# Status_LEDs.net
KiCad netlist of a schematic drawn in Altium Designer
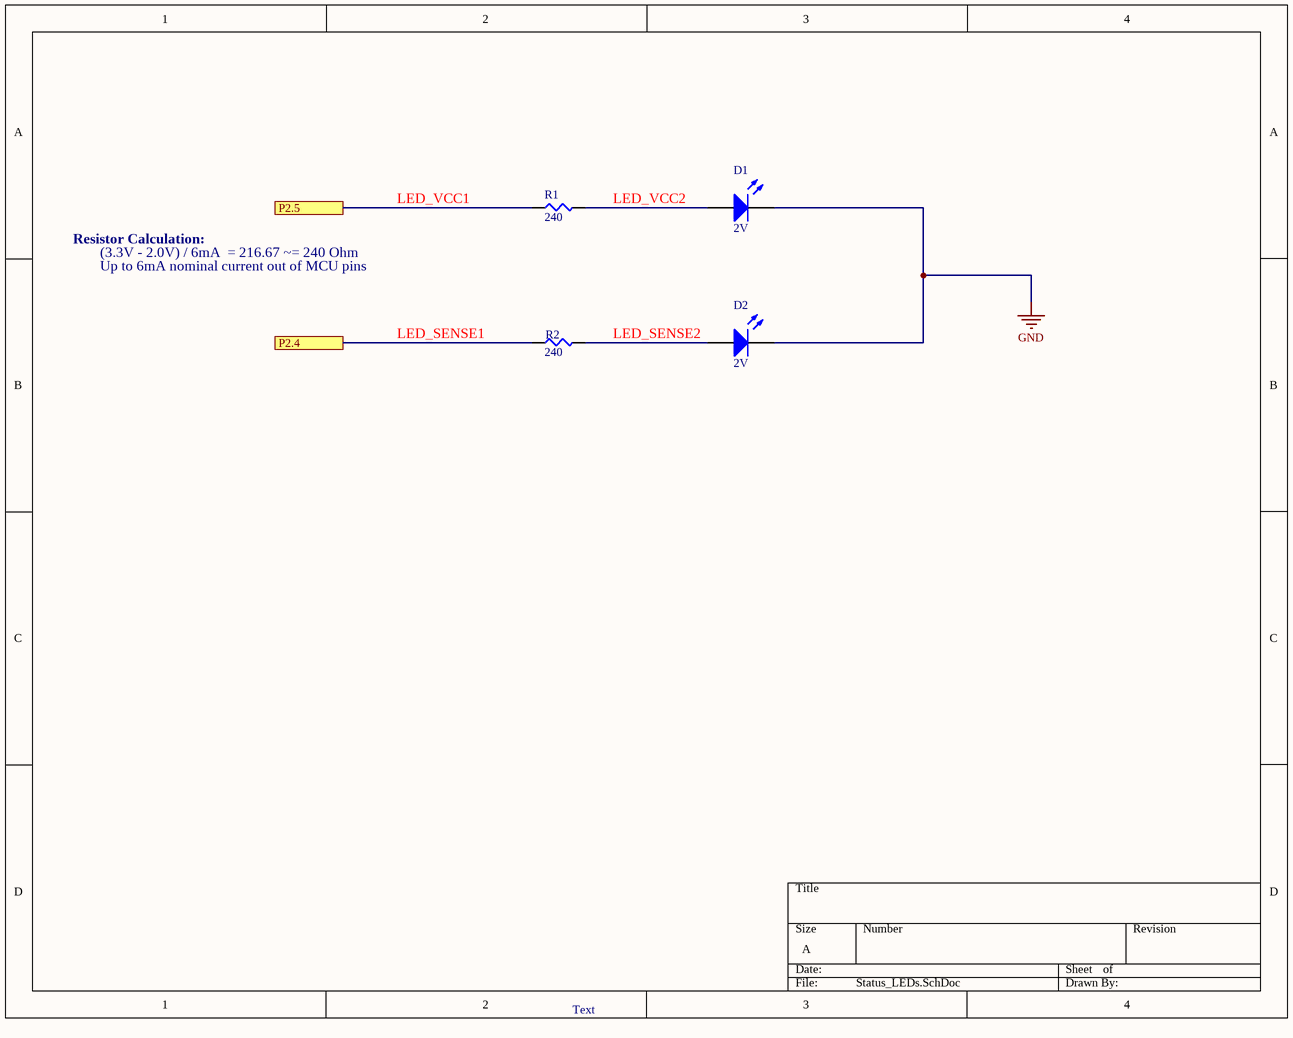
[diagram p0: Status_LEDs.SchDoc]

(export (version "E")
  (design (tool "Eeschema 10.0.6"))
  (components
    (comp (ref "D1")
      (value "2V")
      (footprint "0805_A")
      (description "SMD mono-color Chip LED, WL-SMCW, Bright Green")
      (fields (field (name "PARTNUMBER") "150080VS75000") (field (name "MANUFACTURER") "Wuerth Elektronik"))
      (libsource (lib "Altium Content Vault") (part "WE-LED_K1A2-2"))
    )
    (comp (ref "D2")
      (value "2V")
      (footprint "0805_A")
      (description "SMD mono-color Chip LED, WL-SMCW, Bright Green")
      (fields (field (name "PARTNUMBER") "150080VS75000") (field (name "MANUFACTURER") "Wuerth Elektronik"))
      (libsource (lib "Altium Content Vault") (part "WE-LED_K1A2-2"))
    )
    (comp (ref "R1")
      (value "240")
      (footprint "SMD-0805-RES")
      (description "RES SMD 240 OHM 1% 1/8W 0805")
      (fields (field (name "PART NUMBER") "ERJ-6ENF2400V") (field (name "DIGI-KEY PART NUMBER") "P240CCT-ND"))
      (libsource (lib "Panasonic_resistor_0805") (part "ERJ-6ENF2400V"))
    )
    (comp (ref "R2")
      (value "240")
      (footprint "SMD-0805-RES")
      (description "RES SMD 240 OHM 1% 1/8W 0805")
      (fields (field (name "PART NUMBER") "ERJ-6ENF2400V") (field (name "DIGI-KEY PART NUMBER") "P240CCT-ND"))
      (libsource (lib "Panasonic_resistor_0805") (part "ERJ-6ENF2400V"))
    )
  )
  (nets
    (net (code "1") (name "/P2.4") (class "Default")
      (node (ref "R2") (pin "1") (pinfunction "1_1") (pintype "passive"))
    )
    (net (code "2") (name "/P2.5") (class "Default")
      (node (ref "R1") (pin "1") (pinfunction "1_1") (pintype "passive"))
    )
    (net (code "3") (name "GND") (class "Default")
      (node (ref "D1") (pin "1") (pinfunction "K_1") (pintype "passive"))
      (node (ref "D2") (pin "1") (pinfunction "K_1") (pintype "passive"))
    )
    (net (code "4") (name "Net-(D1-A)") (class "Default")
      (node (ref "D1") (pin "2") (pinfunction "A_2") (pintype "passive"))
      (node (ref "R1") (pin "2") (pinfunction "2_2") (pintype "passive"))
    )
    (net (code "5") (name "Net-(D2-A)") (class "Default")
      (node (ref "D2") (pin "2") (pinfunction "A_2") (pintype "passive"))
      (node (ref "R2") (pin "2") (pinfunction "2_2") (pintype "passive"))
    )
  )
)
